# ITDB02.net
KiCad netlist of a schematic drawn in Altium Designer
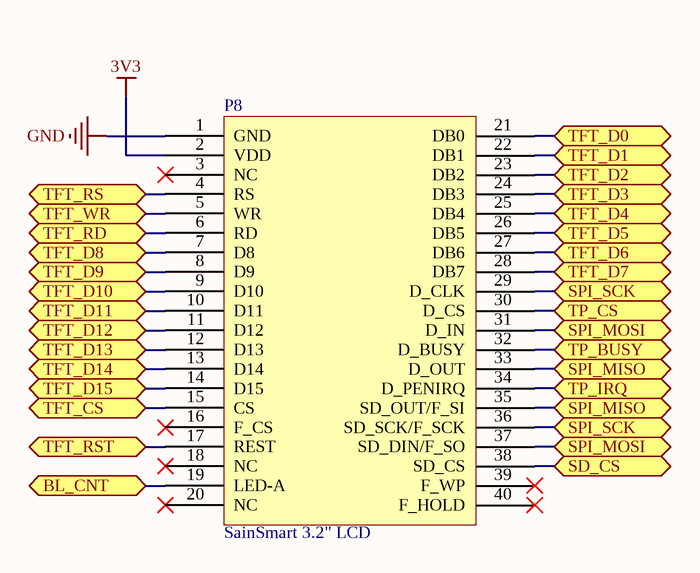
[diagram p0: ITDB02.SchDoc]

(export (version "E")
  (design (tool "Eeschema 10.0.6"))
  (components
    (comp (ref "P8")
      (value "SainSmart 3.2\" LCD")
      (footprint "HDR2x20")
      (libsource (lib "BrewBit") (part "SainSmart 3.2{dblquote} LCD"))
    )
  )
  (nets
    (net (code "1") (name "/BL_CNT") (class "Default")
      (node (ref "P8") (pin "19") (pinfunction "LED-A_19") (pintype "passive"))
    )
    (net (code "2") (name "/SD_CS") (class "Default")
      (node (ref "P8") (pin "38") (pinfunction "SD_CS_38") (pintype "passive"))
    )
    (net (code "3") (name "/SPI_MISO") (class "Default")
      (node (ref "P8") (pin "33") (pinfunction "D_OUT_33") (pintype "passive"))
      (node (ref "P8") (pin "35") (pinfunction "SD_OUT/F_SI_35") (pintype "passive"))
    )
    (net (code "4") (name "/SPI_MOSI") (class "Default")
      (node (ref "P8") (pin "31") (pinfunction "D_IN_31") (pintype "passive"))
      (node (ref "P8") (pin "37") (pinfunction "SD_DIN/F_SO_37") (pintype "passive"))
    )
    (net (code "5") (name "/SPI_SCK") (class "Default")
      (node (ref "P8") (pin "29") (pinfunction "D_CLK_29") (pintype "passive"))
      (node (ref "P8") (pin "36") (pinfunction "SD_SCK/F_SCK_36") (pintype "passive"))
    )
    (net (code "6") (name "/TFT_CS") (class "Default")
      (node (ref "P8") (pin "15") (pinfunction "CS_15") (pintype "passive"))
    )
    (net (code "7") (name "/TFT_D0") (class "Default")
      (node (ref "P8") (pin "21") (pinfunction "DB0_21") (pintype "passive"))
    )
    (net (code "8") (name "/TFT_D1") (class "Default")
      (node (ref "P8") (pin "22") (pinfunction "DB1_22") (pintype "passive"))
    )
    (net (code "9") (name "/TFT_D2") (class "Default")
      (node (ref "P8") (pin "23") (pinfunction "DB2_23") (pintype "passive"))
    )
    (net (code "10") (name "/TFT_D3") (class "Default")
      (node (ref "P8") (pin "24") (pinfunction "DB3_24") (pintype "passive"))
    )
    (net (code "11") (name "/TFT_D4") (class "Default")
      (node (ref "P8") (pin "25") (pinfunction "DB4_25") (pintype "passive"))
    )
    (net (code "12") (name "/TFT_D5") (class "Default")
      (node (ref "P8") (pin "26") (pinfunction "DB5_26") (pintype "passive"))
    )
    (net (code "13") (name "/TFT_D6") (class "Default")
      (node (ref "P8") (pin "27") (pinfunction "DB6_27") (pintype "passive"))
    )
    (net (code "14") (name "/TFT_D7") (class "Default")
      (node (ref "P8") (pin "28") (pinfunction "DB7_28") (pintype "passive"))
    )
    (net (code "15") (name "/TFT_D8") (class "Default")
      (node (ref "P8") (pin "7") (pinfunction "D8_7") (pintype "passive"))
    )
    (net (code "16") (name "/TFT_D9") (class "Default")
      (node (ref "P8") (pin "8") (pinfunction "D9_8") (pintype "passive"))
    )
    (net (code "17") (name "/TFT_D10") (class "Default")
      (node (ref "P8") (pin "9") (pinfunction "D10_9") (pintype "passive"))
    )
    (net (code "18") (name "/TFT_D11") (class "Default")
      (node (ref "P8") (pin "10") (pinfunction "D11_10") (pintype "passive"))
    )
    (net (code "19") (name "/TFT_D12") (class "Default")
      (node (ref "P8") (pin "11") (pinfunction "D12_11") (pintype "passive"))
    )
    (net (code "20") (name "/TFT_D13") (class "Default")
      (node (ref "P8") (pin "12") (pinfunction "D13_12") (pintype "passive"))
    )
    (net (code "21") (name "/TFT_D14") (class "Default")
      (node (ref "P8") (pin "13") (pinfunction "D14_13") (pintype "passive"))
    )
    (net (code "22") (name "/TFT_D15") (class "Default")
      (node (ref "P8") (pin "14") (pinfunction "D15_14") (pintype "passive"))
    )
    (net (code "23") (name "/TFT_RD") (class "Default")
      (node (ref "P8") (pin "6") (pinfunction "RD_6") (pintype "passive"))
    )
    (net (code "24") (name "/TFT_RS") (class "Default")
      (node (ref "P8") (pin "4") (pinfunction "RS_4") (pintype "passive"))
    )
    (net (code "25") (name "/TFT_RST") (class "Default")
      (node (ref "P8") (pin "17") (pinfunction "REST_17") (pintype "passive"))
    )
    (net (code "26") (name "/TFT_WR") (class "Default")
      (node (ref "P8") (pin "5") (pinfunction "WR_5") (pintype "passive"))
    )
    (net (code "27") (name "/TP_BUSY") (class "Default")
      (node (ref "P8") (pin "32") (pinfunction "D_BUSY_32") (pintype "passive"))
    )
    (net (code "28") (name "/TP_CS") (class "Default")
      (node (ref "P8") (pin "30") (pinfunction "D_CS_30") (pintype "passive"))
    )
    (net (code "29") (name "/TP_IRQ") (class "Default")
      (node (ref "P8") (pin "34") (pinfunction "D_PENIRQ_34") (pintype "passive"))
    )
    (net (code "30") (name "3V3") (class "Default")
      (node (ref "P8") (pin "2") (pinfunction "VDD_2") (pintype "passive"))
    )
    (net (code "31") (name "GND") (class "Default")
      (node (ref "P8") (pin "1") (pinfunction "GND_1") (pintype "passive"))
    )
    (net (code "32") (name "unconnected-(P8-F_CS-Pad16)") (class "Default")
      (node (ref "P8") (pin "16") (pinfunction "F_CS_16") (pintype "passive+no_connect"))
    )
    (net (code "33") (name "unconnected-(P8-F_HOLD-Pad40)") (class "Default")
      (node (ref "P8") (pin "40") (pinfunction "F_HOLD_40") (pintype "passive+no_connect"))
    )
    (net (code "34") (name "unconnected-(P8-F_WP-Pad39)") (class "Default")
      (node (ref "P8") (pin "39") (pinfunction "F_WP_39") (pintype "passive+no_connect"))
    )
    (net (code "35") (name "unconnected-(P8-NC-Pad3)") (class "Default")
      (node (ref "P8") (pin "3") (pinfunction "NC_3") (pintype "passive+no_connect"))
    )
    (net (code "36") (name "unconnected-(P8-NC-Pad18)") (class "Default")
      (node (ref "P8") (pin "18") (pinfunction "NC_18") (pintype "passive+no_connect"))
    )
    (net (code "37") (name "unconnected-(P8-NC-Pad20)") (class "Default")
      (node (ref "P8") (pin "20") (pinfunction "NC_20") (pintype "passive+no_connect"))
    )
  )
)
